# Regulator.net
KiCad netlist of a schematic drawn in Altium Designer
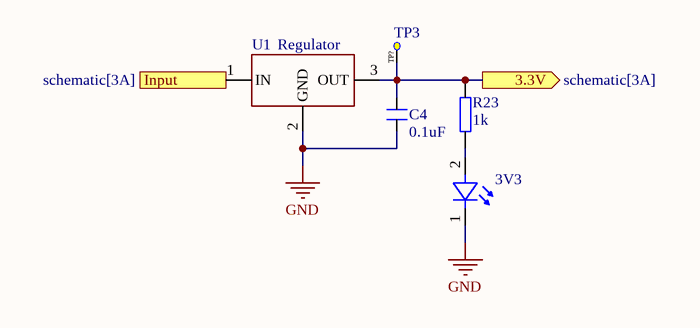
[diagram p0: Regulator.SchDoc]

(export (version "E")
  (design (tool "Eeschema 10.0.6"))
  (components
    (comp (ref "3V3") (value "led") (footprint "LED_fp") (libsource (lib "sch_comp") (part "led")))
    (comp (ref "C4") (value "0.1uF") (footprint "CAP_0805") (libsource (lib "sch_comp") (part "CAP_0805")))
    (comp (ref "R23") (value "1k") (footprint "RES0402") (libsource (lib "sch_comp") (part "RES 0402")))
    (comp (ref "TP3")
      (value "test_point")
      (footprint "Test_point")
      (libsource (lib "sch_comp") (part "test_point"))
    )
    (comp (ref "U1")
      (value "Regulator")
      (footprint "TC1108")
      (description "CJ117 or TC1108")
      (libsource (lib "sch_comp") (part "Regulator"))
    )
  )
  (nets
    (net (code "1") (name "/3.3V") (class "Default")
      (node (ref "C4") (pin "2") (pintype "passive"))
      (node (ref "R23") (pin "2") (pintype "passive"))
      (node (ref "TP3") (pin "TP?") (pinfunction "Test_Point_TP?") (pintype "passive"))
      (node (ref "U1") (pin "3") (pinfunction "OUT_3") (pintype "passive"))
    )
    (net (code "2") (name "/Input") (class "Default")
      (node (ref "U1") (pin "1") (pinfunction "IN_1") (pintype "passive"))
    )
    (net (code "3") (name "GND") (class "Default")
      (node (ref "3V3") (pin "1") (pinfunction "8_1") (pintype "passive"))
      (node (ref "C4") (pin "1") (pintype "passive"))
      (node (ref "U1") (pin "2") (pinfunction "GND_2") (pintype "passive"))
    )
    (net (code "4") (name "Net-(3V3-9)") (class "Default")
      (node (ref "3V3") (pin "2") (pinfunction "9_2") (pintype "passive"))
      (node (ref "R23") (pin "1") (pintype "passive"))
    )
  )
)
